# man_actuation_board_2_4.net
KiCad netlist of a schematic drawn in EAGLE
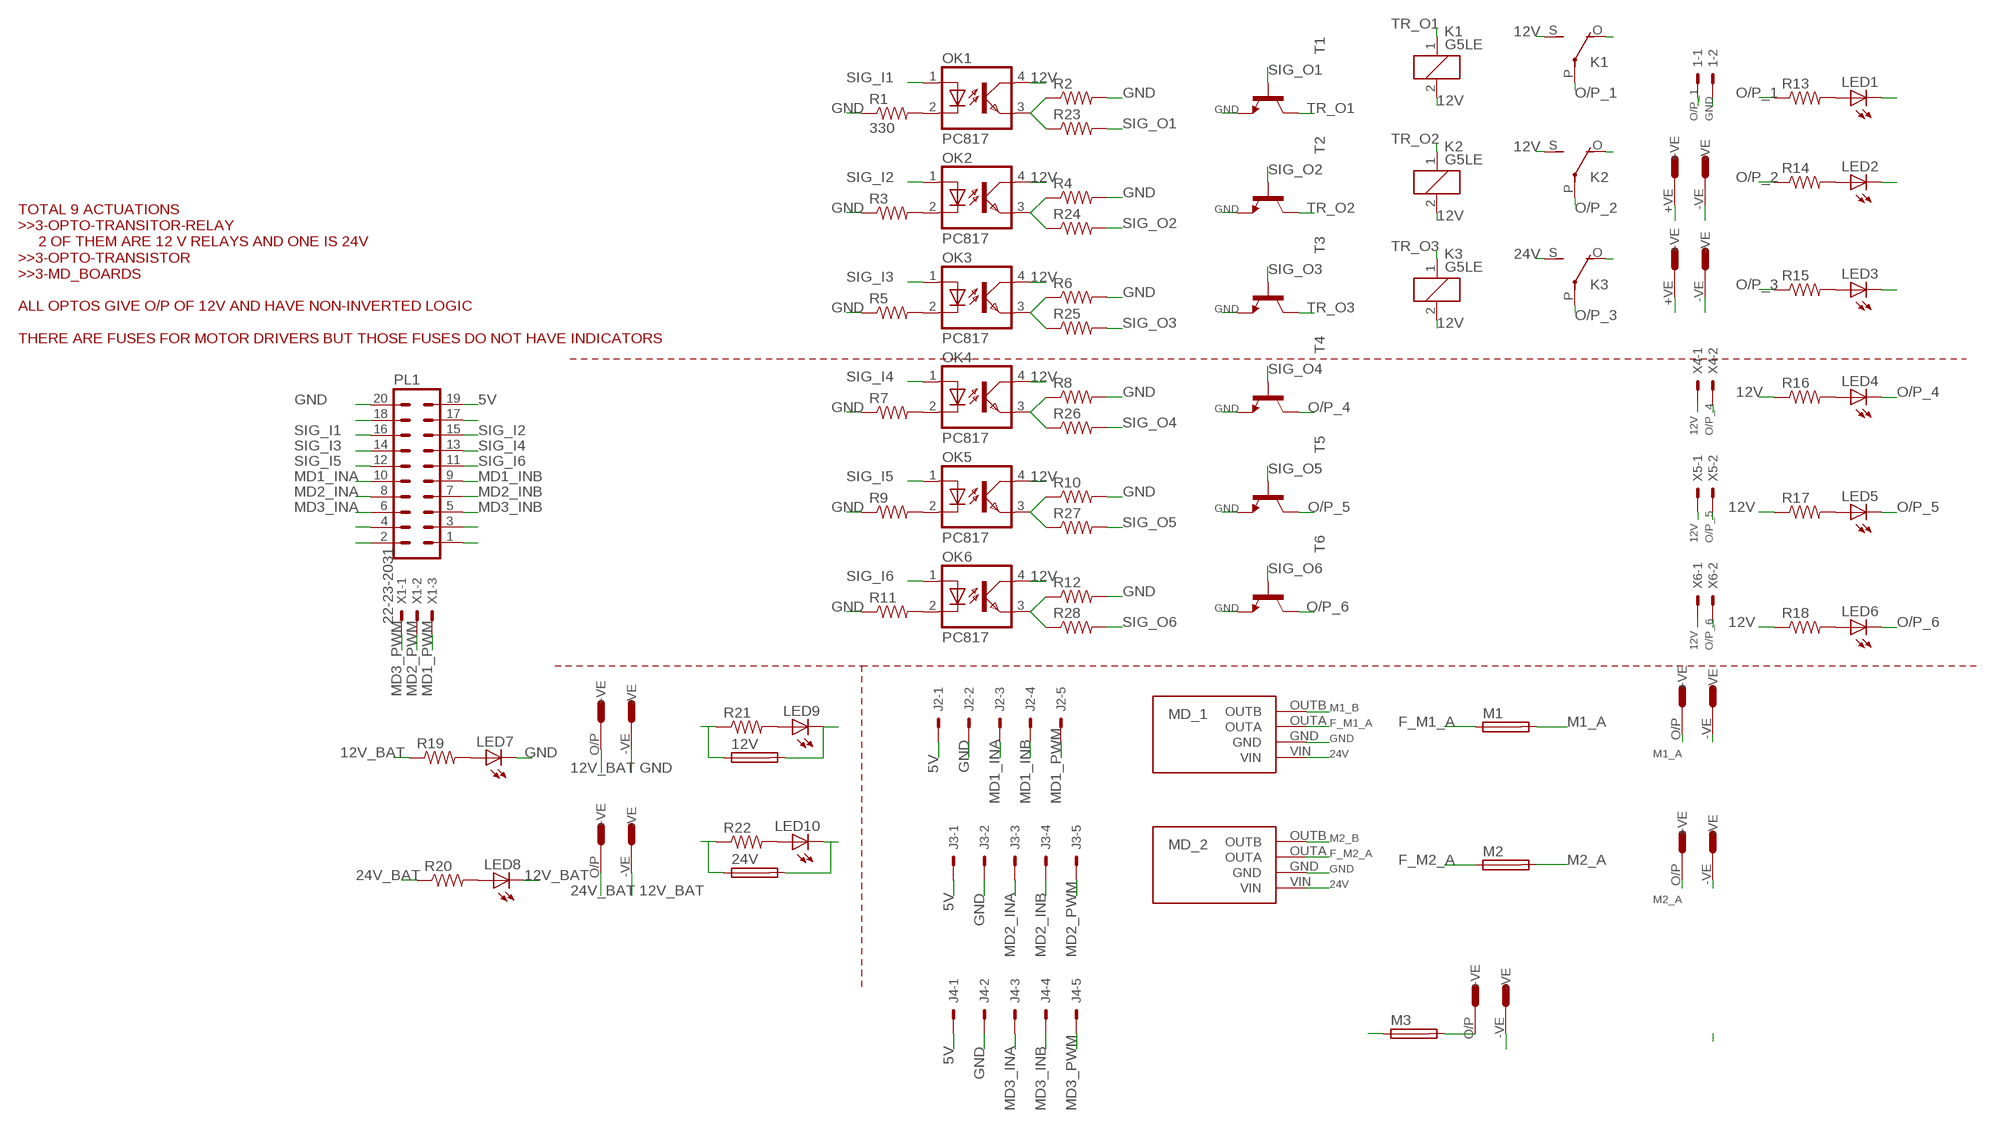
[diagram p0: schematic, sheet 1]

(export (version "E")
  (design (tool "Eeschema 10.0.6"))
  (components
    (comp (ref "0-12_BAT")
      (value "MOLEX_4")
      (footprint "eagle-import:MOLEX_2K14")
      (libsource (lib "eagle-import") (part "MOLEX_4"))
    )
    (comp (ref "1")
      (value "1")
      (footprint "eagle-import:22-23-2021")
      (fields (field (name "MF") "MOLEX") (field (name "MPN") "22-23-2021"))
      (libsource (lib "eagle-import") (part "22-23-2021"))
    )
    (comp (ref "12-24_I/P")
      (value "MOLEX_4")
      (footprint "eagle-import:MOLEX_2K14")
      (libsource (lib "eagle-import") (part "MOLEX_4"))
    )
    (comp (ref "12V")
      (value "SH25")
      (footprint "eagle-import:SH25")
      (fields (field (name "MF") "SCHURTER") (field (name "MPN") "0031.8211"))
      (libsource (lib "eagle-import") (part "SH25"))
    )
    (comp (ref "24V")
      (value "SH25")
      (footprint "eagle-import:SH25")
      (fields (field (name "MF") "SCHURTER") (field (name "MPN") "0031.8211"))
      (libsource (lib "eagle-import") (part "SH25"))
    )
    (comp (ref "J2")
      (value "22-27-2051-05")
      (footprint "eagle-import:6410-05")
      (libsource (lib "eagle-import") (part "22-?-0527-2051"))
    )
    (comp (ref "J3")
      (value "22-27-2051-05")
      (footprint "eagle-import:6410-05")
      (libsource (lib "eagle-import") (part "22-?-0527-2051"))
    )
    (comp (ref "J4")
      (value "22-27-2051-05")
      (footprint "eagle-import:6410-05")
      (libsource (lib "eagle-import") (part "22-?-0527-2051"))
    )
    (comp (ref "K1")
      (value "G5LE")
      (footprint "eagle-import:G5LE")
      (libsource (lib "eagle-import") (part "G5LE"))
    )
    (comp (ref "K2")
      (value "G5LE")
      (footprint "eagle-import:G5LE")
      (libsource (lib "eagle-import") (part "G5LE"))
    )
    (comp (ref "K3")
      (value "G5LE")
      (footprint "eagle-import:G5LE")
      (libsource (lib "eagle-import") (part "G5LE"))
    )
    (comp (ref "LED1")
      (value "LED1206")
      (footprint "eagle-import:LED-1206")
      (libsource (lib "eagle-import") (part "LED1206"))
    )
    (comp (ref "LED2")
      (value "LED1206")
      (footprint "eagle-import:LED-1206")
      (libsource (lib "eagle-import") (part "LED1206"))
    )
    (comp (ref "LED3")
      (value "LED1206")
      (footprint "eagle-import:LED-1206")
      (libsource (lib "eagle-import") (part "LED1206"))
    )
    (comp (ref "LED4")
      (value "LED1206")
      (footprint "eagle-import:LED-1206")
      (libsource (lib "eagle-import") (part "LED1206"))
    )
    (comp (ref "LED5")
      (value "LED1206")
      (footprint "eagle-import:LED-1206")
      (libsource (lib "eagle-import") (part "LED1206"))
    )
    (comp (ref "LED6")
      (value "LED1206")
      (footprint "eagle-import:LED-1206")
      (libsource (lib "eagle-import") (part "LED1206"))
    )
    (comp (ref "LED7")
      (value "LED1206")
      (footprint "eagle-import:LED-1206")
      (libsource (lib "eagle-import") (part "LED1206"))
    )
    (comp (ref "LED8")
      (value "LED1206")
      (footprint "eagle-import:LED-1206")
      (libsource (lib "eagle-import") (part "LED1206"))
    )
    (comp (ref "LED9")
      (value "LED1206")
      (footprint "eagle-import:LED-1206")
      (libsource (lib "eagle-import") (part "LED1206"))
    )
    (comp (ref "LED10")
      (value "LED1206")
      (footprint "eagle-import:LED-1206")
      (libsource (lib "eagle-import") (part "LED1206"))
    )
    (comp (ref "M1")
      (value "SH25")
      (footprint "eagle-import:SH25")
      (fields (field (name "MF") "SCHURTER") (field (name "MPN") "0031.8211"))
      (libsource (lib "eagle-import") (part "SH25"))
    )
    (comp (ref "M2")
      (value "SH25")
      (footprint "eagle-import:SH25")
      (fields (field (name "MF") "SCHURTER") (field (name "MPN") "0031.8211"))
      (libsource (lib "eagle-import") (part "SH25"))
    )
    (comp (ref "M3")
      (value "SH25")
      (footprint "eagle-import:SH25")
      (fields (field (name "MF") "SCHURTER") (field (name "MPN") "0031.8211"))
      (libsource (lib "eagle-import") (part "SH25"))
    )
    (comp (ref "MD_1")
      (value "MOTOR_DRIVER")
      (footprint "eagle-import:MOTOR_DRIVER")
      (libsource (lib "eagle-import") (part "MOTOR_DRIVER"))
    )
    (comp (ref "MD_2")
      (value "MOTOR_DRIVER")
      (footprint "eagle-import:MOTOR_DRIVER")
      (libsource (lib "eagle-import") (part "MOTOR_DRIVER"))
    )
    (comp (ref "OK1")
      (value "PC817")
      (footprint "eagle-import:DIL04")
      (fields (field (name "MPN") "PC817X4J000F"))
      (libsource (lib "eagle-import") (part "PC817"))
    )
    (comp (ref "OK2")
      (value "PC817")
      (footprint "eagle-import:DIL04")
      (fields (field (name "MPN") "PC817X4J000F"))
      (libsource (lib "eagle-import") (part "PC817"))
    )
    (comp (ref "OK3")
      (value "PC817")
      (footprint "eagle-import:DIL04")
      (fields (field (name "MPN") "PC817X4J000F"))
      (libsource (lib "eagle-import") (part "PC817"))
    )
    (comp (ref "OK4")
      (value "PC817")
      (footprint "eagle-import:DIL04")
      (fields (field (name "MPN") "PC817X4J000F"))
      (libsource (lib "eagle-import") (part "PC817"))
    )
    (comp (ref "OK5")
      (value "PC817")
      (footprint "eagle-import:DIL04")
      (fields (field (name "MPN") "PC817X4J000F"))
      (libsource (lib "eagle-import") (part "PC817"))
    )
    (comp (ref "OK6")
      (value "PC817")
      (footprint "eagle-import:DIL04")
      (fields (field (name "MPN") "PC817X4J000F"))
      (libsource (lib "eagle-import") (part "PC817"))
    )
    (comp (ref "PL1")
      (value "ML20ML20")
      (footprint "eagle-import:ML20")
      (libsource (lib "eagle-import") (part "ML20ML20"))
    )
    (comp (ref "R1")
      (value "330")
      (footprint "eagle-import:1206")
      (libsource (lib "eagle-import") (part "RESISTOR1206"))
    )
    (comp (ref "R2")
      (value "RESISTOR1206")
      (footprint "eagle-import:1206")
      (libsource (lib "eagle-import") (part "RESISTOR1206"))
    )
    (comp (ref "R3")
      (value "RESISTOR1206")
      (footprint "eagle-import:1206")
      (libsource (lib "eagle-import") (part "RESISTOR1206"))
    )
    (comp (ref "R4")
      (value "RESISTOR1206")
      (footprint "eagle-import:1206")
      (libsource (lib "eagle-import") (part "RESISTOR1206"))
    )
    (comp (ref "R5")
      (value "RESISTOR1206")
      (footprint "eagle-import:1206")
      (libsource (lib "eagle-import") (part "RESISTOR1206"))
    )
    (comp (ref "R6")
      (value "RESISTOR1206")
      (footprint "eagle-import:1206")
      (libsource (lib "eagle-import") (part "RESISTOR1206"))
    )
    (comp (ref "R7")
      (value "RESISTOR1206")
      (footprint "eagle-import:1206")
      (libsource (lib "eagle-import") (part "RESISTOR1206"))
    )
    (comp (ref "R8")
      (value "RESISTOR1206")
      (footprint "eagle-import:1206")
      (libsource (lib "eagle-import") (part "RESISTOR1206"))
    )
    (comp (ref "R9")
      (value "RESISTOR1206")
      (footprint "eagle-import:1206")
      (libsource (lib "eagle-import") (part "RESISTOR1206"))
    )
    (comp (ref "R10")
      (value "RESISTOR1206")
      (footprint "eagle-import:1206")
      (libsource (lib "eagle-import") (part "RESISTOR1206"))
    )
    (comp (ref "R11")
      (value "RESISTOR1206")
      (footprint "eagle-import:1206")
      (libsource (lib "eagle-import") (part "RESISTOR1206"))
    )
    (comp (ref "R12")
      (value "RESISTOR1206")
      (footprint "eagle-import:1206")
      (libsource (lib "eagle-import") (part "RESISTOR1206"))
    )
    (comp (ref "R13")
      (value "RESISTOR1206")
      (footprint "eagle-import:1206")
      (libsource (lib "eagle-import") (part "RESISTOR1206"))
    )
    (comp (ref "R14")
      (value "RESISTOR1206")
      (footprint "eagle-import:1206")
      (libsource (lib "eagle-import") (part "RESISTOR1206"))
    )
    (comp (ref "R15")
      (value "RESISTOR1206")
      (footprint "eagle-import:1206")
      (libsource (lib "eagle-import") (part "RESISTOR1206"))
    )
    (comp (ref "R16")
      (value "RESISTOR1206")
      (footprint "eagle-import:1206")
      (libsource (lib "eagle-import") (part "RESISTOR1206"))
    )
    (comp (ref "R17")
      (value "RESISTOR1206")
      (footprint "eagle-import:1206")
      (libsource (lib "eagle-import") (part "RESISTOR1206"))
    )
    (comp (ref "R18")
      (value "RESISTOR1206")
      (footprint "eagle-import:1206")
      (libsource (lib "eagle-import") (part "RESISTOR1206"))
    )
    (comp (ref "R19")
      (value "RESISTOR1206")
      (footprint "eagle-import:1206")
      (libsource (lib "eagle-import") (part "RESISTOR1206"))
    )
    (comp (ref "R20")
      (value "RESISTOR1206")
      (footprint "eagle-import:1206")
      (libsource (lib "eagle-import") (part "RESISTOR1206"))
    )
    (comp (ref "R21")
      (value "RESISTOR1206")
      (footprint "eagle-import:1206")
      (libsource (lib "eagle-import") (part "RESISTOR1206"))
    )
    (comp (ref "R22")
      (value "RESISTOR1206")
      (footprint "eagle-import:1206")
      (libsource (lib "eagle-import") (part "RESISTOR1206"))
    )
    (comp (ref "R23")
      (value "RESISTOR1206")
      (footprint "eagle-import:1206")
      (libsource (lib "eagle-import") (part "RESISTOR1206"))
    )
    (comp (ref "R24")
      (value "RESISTOR1206")
      (footprint "eagle-import:1206")
      (libsource (lib "eagle-import") (part "RESISTOR1206"))
    )
    (comp (ref "R25")
      (value "RESISTOR1206")
      (footprint "eagle-import:1206")
      (libsource (lib "eagle-import") (part "RESISTOR1206"))
    )
    (comp (ref "R26")
      (value "RESISTOR1206")
      (footprint "eagle-import:1206")
      (libsource (lib "eagle-import") (part "RESISTOR1206"))
    )
    (comp (ref "R27")
      (value "RESISTOR1206")
      (footprint "eagle-import:1206")
      (libsource (lib "eagle-import") (part "RESISTOR1206"))
    )
    (comp (ref "R28")
      (value "RESISTOR1206")
      (footprint "eagle-import:1206")
      (libsource (lib "eagle-import") (part "RESISTOR1206"))
    )
    (comp (ref "T1")
      (value "-NPN-TO5")
      (footprint "eagle-import:TO5")
      (libsource (lib "eagle-import") (part "-NPN-TO5"))
    )
    (comp (ref "T2")
      (value "-NPN-TO5")
      (footprint "eagle-import:TO5")
      (libsource (lib "eagle-import") (part "-NPN-TO5"))
    )
    (comp (ref "T3")
      (value "-NPN-TO5")
      (footprint "eagle-import:TO5")
      (libsource (lib "eagle-import") (part "-NPN-TO5"))
    )
    (comp (ref "T4")
      (value "-NPN-TO5")
      (footprint "eagle-import:TO5")
      (libsource (lib "eagle-import") (part "-NPN-TO5"))
    )
    (comp (ref "T5")
      (value "-NPN-TO5")
      (footprint "eagle-import:TO5")
      (libsource (lib "eagle-import") (part "-NPN-TO5"))
    )
    (comp (ref "T6")
      (value "-NPN-TO5")
      (footprint "eagle-import:TO5")
      (libsource (lib "eagle-import") (part "-NPN-TO5"))
    )
    (comp (ref "U$1")
      (value "MOLEX_4")
      (footprint "eagle-import:MOLEX_2K14")
      (libsource (lib "eagle-import") (part "MOLEX_4"))
    )
    (comp (ref "U$2")
      (value "MOLEX_4")
      (footprint "eagle-import:MOLEX_2K14")
      (libsource (lib "eagle-import") (part "MOLEX_4"))
    )
    (comp (ref "U$3")
      (value "MOLEX_4")
      (footprint "eagle-import:MOLEX_2K14")
      (libsource (lib "eagle-import") (part "MOLEX_4"))
    )
    (comp (ref "U$4")
      (value "MOLEXM")
      (footprint "eagle-import:MOLEX_2K13")
      (libsource (lib "eagle-import") (part "MOLEXM"))
    )
    (comp (ref "U$5")
      (value "MOLEXM")
      (footprint "eagle-import:MOLEX_2K13")
      (libsource (lib "eagle-import") (part "MOLEXM"))
    )
    (comp (ref "X1")
      (value "22-23-2031")
      (footprint "eagle-import:22-23-2031")
      (fields (field (name "MF") "MOLEX"))
      (libsource (lib "eagle-import") (part "22-23-2031"))
    )
    (comp (ref "X4")
      (value "4")
      (footprint "eagle-import:22-23-2021")
      (fields (field (name "MF") "MOLEX") (field (name "MPN") "22-23-2021"))
      (libsource (lib "eagle-import") (part "22-23-2021"))
    )
    (comp (ref "X5")
      (value "5")
      (footprint "eagle-import:22-23-2021")
      (fields (field (name "MF") "MOLEX") (field (name "MPN") "22-23-2021"))
      (libsource (lib "eagle-import") (part "22-23-2021"))
    )
    (comp (ref "X6")
      (value "6")
      (footprint "eagle-import:22-23-2021")
      (fields (field (name "MF") "MOLEX") (field (name "MPN") "22-23-2021"))
      (libsource (lib "eagle-import") (part "22-23-2021"))
    )
  )
  (nets
    (net (code "1") (name "/5V") (class "Default")
      (node (ref "J2") (pin "1") (pinfunction "S_1") (pintype "passive"))
      (node (ref "J3") (pin "1") (pinfunction "S_1") (pintype "passive"))
      (node (ref "J4") (pin "1") (pinfunction "S_1") (pintype "passive"))
      (node (ref "PL1") (pin "19") (pinfunction "19_19") (pintype "passive"))
    )
    (net (code "2") (name "/12V") (class "Default")
      (node (ref "12V") (pin "2") (pinfunction "2_2") (pintype "passive"))
      (node (ref "K1") (pin "2") (pinfunction "2_2") (pintype "passive"))
      (node (ref "K1") (pin "S") (pinfunction "S_S") (pintype "passive"))
      (node (ref "K2") (pin "2") (pinfunction "2_2") (pintype "passive"))
      (node (ref "K2") (pin "S") (pinfunction "S_S") (pintype "passive"))
      (node (ref "K3") (pin "2") (pinfunction "2_2") (pintype "passive"))
      (node (ref "LED9") (pin "C") (pinfunction "C_C") (pintype "passive"))
      (node (ref "OK1") (pin "4") (pinfunction "COL_4") (pintype "passive"))
      (node (ref "OK2") (pin "4") (pinfunction "COL_4") (pintype "passive"))
      (node (ref "OK3") (pin "4") (pinfunction "COL_4") (pintype "passive"))
      (node (ref "OK4") (pin "4") (pinfunction "COL_4") (pintype "passive"))
      (node (ref "OK5") (pin "4") (pinfunction "COL_4") (pintype "passive"))
      (node (ref "OK6") (pin "4") (pinfunction "COL_4") (pintype "passive"))
      (node (ref "R16") (pin "1") (pinfunction "1_1") (pintype "passive"))
      (node (ref "R17") (pin "1") (pinfunction "1_1") (pintype "passive"))
      (node (ref "R18") (pin "1") (pinfunction "1_1") (pintype "passive"))
      (node (ref "X4") (pin "1") (pinfunction "S_1") (pintype "passive"))
      (node (ref "X5") (pin "1") (pinfunction "S_1") (pintype "passive"))
      (node (ref "X6") (pin "1") (pinfunction "S_1") (pintype "passive"))
    )
    (net (code "3") (name "/12V_BAT") (class "Default")
      (node (ref "0-12_BAT") (pin "O/P") (pinfunction "+VE_O/P") (pintype "bidirectional"))
      (node (ref "12-24_I/P") (pin "-VE") (pinfunction "-VE_-VE") (pintype "bidirectional"))
      (node (ref "12V") (pin "1") (pinfunction "1_1") (pintype "passive"))
      (node (ref "LED8") (pin "C") (pinfunction "C_C") (pintype "passive"))
      (node (ref "R19") (pin "1") (pinfunction "1_1") (pintype "passive"))
      (node (ref "R21") (pin "1") (pinfunction "1_1") (pintype "passive"))
    )
    (net (code "4") (name "/24V") (class "Default")
      (node (ref "24V") (pin "2") (pinfunction "2_2") (pintype "passive"))
      (node (ref "K3") (pin "S") (pinfunction "S_S") (pintype "passive"))
      (node (ref "LED10") (pin "C") (pinfunction "C_C") (pintype "passive"))
      (node (ref "M3") (pin "1") (pinfunction "1_1") (pintype "passive"))
      (node (ref "MD_1") (pin "VIN") (pinfunction "VIN_VIN") (pintype "bidirectional"))
      (node (ref "MD_2") (pin "VIN") (pinfunction "VIN_VIN") (pintype "bidirectional"))
    )
    (net (code "5") (name "/24V_BAT") (class "Default")
      (node (ref "12-24_I/P") (pin "O/P") (pinfunction "+VE_O/P") (pintype "bidirectional"))
      (node (ref "24V") (pin "1") (pinfunction "1_1") (pintype "passive"))
      (node (ref "R20") (pin "1") (pinfunction "1_1") (pintype "passive"))
      (node (ref "R22") (pin "1") (pinfunction "1_1") (pintype "passive"))
    )
    (net (code "6") (name "/F_M1_A") (class "Default")
      (node (ref "M1") (pin "1") (pinfunction "1_1") (pintype "passive"))
      (node (ref "MD_1") (pin "OUTA") (pinfunction "OUTA_OUTA") (pintype "bidirectional"))
    )
    (net (code "7") (name "/F_M2_A") (class "Default")
      (node (ref "M2") (pin "1") (pinfunction "1_1") (pintype "passive"))
      (node (ref "MD_2") (pin "OUTA") (pinfunction "OUTA_OUTA") (pintype "bidirectional"))
    )
    (net (code "8") (name "/GND") (class "Default")
      (node (ref "0-12_BAT") (pin "-VE") (pinfunction "-VE_-VE") (pintype "bidirectional"))
      (node (ref "1") (pin "2") (pinfunction "S_2") (pintype "passive"))
      (node (ref "J2") (pin "2") (pinfunction "S_2") (pintype "passive"))
      (node (ref "J3") (pin "2") (pinfunction "S_2") (pintype "passive"))
      (node (ref "J4") (pin "2") (pinfunction "S_2") (pintype "passive"))
      (node (ref "LED1") (pin "C") (pinfunction "C_C") (pintype "passive"))
      (node (ref "LED2") (pin "C") (pinfunction "C_C") (pintype "passive"))
      (node (ref "LED3") (pin "C") (pinfunction "C_C") (pintype "passive"))
      (node (ref "LED7") (pin "C") (pinfunction "C_C") (pintype "passive"))
      (node (ref "MD_1") (pin "GND") (pinfunction "GND_GND") (pintype "bidirectional"))
      (node (ref "MD_2") (pin "GND") (pinfunction "GND_GND") (pintype "bidirectional"))
      (node (ref "PL1") (pin "20") (pinfunction "20_20") (pintype "passive"))
      (node (ref "R1") (pin "1") (pinfunction "1_1") (pintype "passive"))
      (node (ref "R10") (pin "2") (pinfunction "2_2") (pintype "passive"))
      (node (ref "R11") (pin "1") (pinfunction "1_1") (pintype "passive"))
      (node (ref "R12") (pin "2") (pinfunction "2_2") (pintype "passive"))
      (node (ref "R2") (pin "2") (pinfunction "2_2") (pintype "passive"))
      (node (ref "R3") (pin "1") (pinfunction "1_1") (pintype "passive"))
      (node (ref "R4") (pin "2") (pinfunction "2_2") (pintype "passive"))
      (node (ref "R5") (pin "1") (pinfunction "1_1") (pintype "passive"))
      (node (ref "R6") (pin "2") (pinfunction "2_2") (pintype "passive"))
      (node (ref "R7") (pin "1") (pinfunction "1_1") (pintype "passive"))
      (node (ref "R8") (pin "2") (pinfunction "2_2") (pintype "passive"))
      (node (ref "R9") (pin "1") (pinfunction "1_1") (pintype "passive"))
      (node (ref "T1") (pin "1") (pinfunction "E_1") (pintype "passive"))
      (node (ref "T2") (pin "1") (pinfunction "E_1") (pintype "passive"))
      (node (ref "T3") (pin "1") (pinfunction "E_1") (pintype "passive"))
      (node (ref "T4") (pin "1") (pinfunction "E_1") (pintype "passive"))
      (node (ref "T5") (pin "1") (pinfunction "E_1") (pintype "passive"))
      (node (ref "T6") (pin "1") (pinfunction "E_1") (pintype "passive"))
      (node (ref "U$3") (pin "-VE") (pinfunction "-VE_-VE") (pintype "bidirectional"))
      (node (ref "U$4") (pin "-VE") (pinfunction "-VE_-VE") (pintype "bidirectional"))
      (node (ref "U$5") (pin "-VE") (pinfunction "-VE_-VE") (pintype "bidirectional"))
    )
    (net (code "9") (name "/M1_A") (class "Default")
      (node (ref "M1") (pin "2") (pinfunction "2_2") (pintype "passive"))
      (node (ref "U$1") (pin "O/P") (pinfunction "+VE_O/P") (pintype "bidirectional"))
    )
    (net (code "10") (name "/M1_B") (class "Default")
      (node (ref "MD_1") (pin "OUTB") (pinfunction "OUTB_OUTB") (pintype "bidirectional"))
      (node (ref "U$1") (pin "-VE") (pinfunction "-VE_-VE") (pintype "bidirectional"))
    )
    (net (code "11") (name "/M2_A") (class "Default")
      (node (ref "M2") (pin "2") (pinfunction "2_2") (pintype "passive"))
      (node (ref "U$2") (pin "O/P") (pinfunction "+VE_O/P") (pintype "bidirectional"))
    )
    (net (code "12") (name "/M2_B") (class "Default")
      (node (ref "MD_2") (pin "OUTB") (pinfunction "OUTB_OUTB") (pintype "bidirectional"))
      (node (ref "U$2") (pin "-VE") (pinfunction "-VE_-VE") (pintype "bidirectional"))
    )
    (net (code "13") (name "/MD1_INA") (class "Default")
      (node (ref "J2") (pin "3") (pinfunction "S_3") (pintype "passive"))
      (node (ref "PL1") (pin "10") (pinfunction "10_10") (pintype "passive"))
    )
    (net (code "14") (name "/MD1_INB") (class "Default")
      (node (ref "J2") (pin "4") (pinfunction "S_4") (pintype "passive"))
      (node (ref "PL1") (pin "9") (pinfunction "9_9") (pintype "passive"))
    )
    (net (code "15") (name "/MD1_PWM") (class "Default")
      (node (ref "J2") (pin "5") (pinfunction "S_5") (pintype "passive"))
      (node (ref "X1") (pin "3") (pinfunction "S_3") (pintype "passive"))
    )
    (net (code "16") (name "/MD2_INA") (class "Default")
      (node (ref "J3") (pin "3") (pinfunction "S_3") (pintype "passive"))
      (node (ref "PL1") (pin "8") (pinfunction "8_8") (pintype "passive"))
    )
    (net (code "17") (name "/MD2_INB") (class "Default")
      (node (ref "J3") (pin "4") (pinfunction "S_4") (pintype "passive"))
      (node (ref "PL1") (pin "7") (pinfunction "7_7") (pintype "passive"))
    )
    (net (code "18") (name "/MD2_PWM") (class "Default")
      (node (ref "J3") (pin "5") (pinfunction "S_5") (pintype "passive"))
      (node (ref "X1") (pin "2") (pinfunction "S_2") (pintype "passive"))
    )
    (net (code "19") (name "/MD3_INA") (class "Default")
      (node (ref "J4") (pin "3") (pinfunction "S_3") (pintype "passive"))
      (node (ref "PL1") (pin "6") (pinfunction "6_6") (pintype "passive"))
    )
    (net (code "20") (name "/MD3_INB") (class "Default")
      (node (ref "J4") (pin "4") (pinfunction "S_4") (pintype "passive"))
      (node (ref "PL1") (pin "5") (pinfunction "5_5") (pintype "passive"))
    )
    (net (code "21") (name "/MD3_PWM") (class "Default")
      (node (ref "J4") (pin "5") (pinfunction "S_5") (pintype "passive"))
      (node (ref "X1") (pin "1") (pinfunction "S_1") (pintype "passive"))
    )
    (net (code "22") (name "/O{slash}P_1") (class "Default")
      (node (ref "1") (pin "1") (pinfunction "S_1") (pintype "passive"))
      (node (ref "K1") (pin "P") (pinfunction "P_P") (pintype "passive"))
      (node (ref "R13") (pin "1") (pinfunction "1_1") (pintype "passive"))
    )
    (net (code "23") (name "/O{slash}P_2") (class "Default")
      (node (ref "K2") (pin "P") (pinfunction "P_P") (pintype "passive"))
      (node (ref "R14") (pin "1") (pinfunction "1_1") (pintype "passive"))
      (node (ref "U$5") (pin "+VE") (pinfunction "+VE_+VE") (pintype "bidirectional"))
    )
    (net (code "24") (name "/O{slash}P_3") (class "Default")
      (node (ref "K3") (pin "P") (pinfunction "P_P") (pintype "passive"))
      (node (ref "R15") (pin "1") (pinfunction "1_1") (pintype "passive"))
      (node (ref "U$4") (pin "+VE") (pinfunction "+VE_+VE") (pintype "bidirectional"))
    )
    (net (code "25") (name "/O{slash}P_4") (class "Default")
      (node (ref "LED4") (pin "C") (pinfunction "C_C") (pintype "passive"))
      (node (ref "T4") (pin "3") (pinfunction "C_3") (pintype "passive"))
      (node (ref "X4") (pin "2") (pinfunction "S_2") (pintype "passive"))
    )
    (net (code "26") (name "/O{slash}P_5") (class "Default")
      (node (ref "LED5") (pin "C") (pinfunction "C_C") (pintype "passive"))
      (node (ref "T5") (pin "3") (pinfunction "C_3") (pintype "passive"))
      (node (ref "X5") (pin "2") (pinfunction "S_2") (pintype "passive"))
    )
    (net (code "27") (name "/O{slash}P_6") (class "Default")
      (node (ref "LED6") (pin "C") (pinfunction "C_C") (pintype "passive"))
      (node (ref "T6") (pin "3") (pinfunction "C_3") (pintype "passive"))
      (node (ref "X6") (pin "2") (pinfunction "S_2") (pintype "passive"))
    )
    (net (code "28") (name "/SIG_I1") (class "Default")
      (node (ref "OK1") (pin "1") (pinfunction "A_1") (pintype "passive"))
      (node (ref "PL1") (pin "16") (pinfunction "16_16") (pintype "passive"))
    )
    (net (code "29") (name "/SIG_I2") (class "Default")
      (node (ref "OK2") (pin "1") (pinfunction "A_1") (pintype "passive"))
      (node (ref "PL1") (pin "15") (pinfunction "15_15") (pintype "passive"))
    )
    (net (code "30") (name "/SIG_I3") (class "Default")
      (node (ref "OK3") (pin "1") (pinfunction "A_1") (pintype "passive"))
      (node (ref "PL1") (pin "14") (pinfunction "14_14") (pintype "passive"))
    )
    (net (code "31") (name "/SIG_I4") (class "Default")
      (node (ref "OK4") (pin "1") (pinfunction "A_1") (pintype "passive"))
      (node (ref "PL1") (pin "13") (pinfunction "13_13") (pintype "passive"))
    )
    (net (code "32") (name "/SIG_I5") (class "Default")
      (node (ref "OK5") (pin "1") (pinfunction "A_1") (pintype "passive"))
      (node (ref "PL1") (pin "12") (pinfunction "12_12") (pintype "passive"))
    )
    (net (code "33") (name "/SIG_I6") (class "Default")
      (node (ref "OK6") (pin "1") (pinfunction "A_1") (pintype "passive"))
      (node (ref "PL1") (pin "11") (pinfunction "11_11") (pintype "passive"))
    )
    (net (code "34") (name "/SIG_O1") (class "Default")
      (node (ref "R23") (pin "2") (pinfunction "2_2") (pintype "passive"))
      (node (ref "T1") (pin "2") (pinfunction "B_2") (pintype "passive"))
    )
    (net (code "35") (name "/SIG_O2") (class "Default")
      (node (ref "R24") (pin "2") (pinfunction "2_2") (pintype "passive"))
      (node (ref "T2") (pin "2") (pinfunction "B_2") (pintype "passive"))
    )
    (net (code "36") (name "/SIG_O3") (class "Default")
      (node (ref "R25") (pin "2") (pinfunction "2_2") (pintype "passive"))
      (node (ref "T3") (pin "2") (pinfunction "B_2") (pintype "passive"))
    )
    (net (code "37") (name "/SIG_O4") (class "Default")
      (node (ref "R26") (pin "2") (pinfunction "2_2") (pintype "passive"))
      (node (ref "T4") (pin "2") (pinfunction "B_2") (pintype "passive"))
    )
    (net (code "38") (name "/SIG_O5") (class "Default")
      (node (ref "R27") (pin "2") (pinfunction "2_2") (pintype "passive"))
      (node (ref "T5") (pin "2") (pinfunction "B_2") (pintype "passive"))
    )
    (net (code "39") (name "/SIG_O6") (class "Default")
      (node (ref "R28") (pin "2") (pinfunction "2_2") (pintype "passive"))
      (node (ref "T6") (pin "2") (pinfunction "B_2") (pintype "passive"))
    )
    (net (code "40") (name "/TR_O1") (class "Default")
      (node (ref "K1") (pin "1") (pinfunction "1_1") (pintype "passive"))
      (node (ref "T1") (pin "3") (pinfunction "C_3") (pintype "passive"))
    )
    (net (code "41") (name "/TR_O2") (class "Default")
      (node (ref "K2") (pin "1") (pinfunction "1_1") (pintype "passive"))
      (node (ref "T2") (pin "3") (pinfunction "C_3") (pintype "passive"))
    )
    (net (code "42") (name "/TR_O3") (class "Default")
      (node (ref "K3") (pin "1") (pinfunction "1_1") (pintype "passive"))
      (node (ref "T3") (pin "3") (pinfunction "C_3") (pintype "passive"))
    )
    (net (code "43") (name "Net-(LED1-PadA)") (class "Default")
      (node (ref "LED1") (pin "A") (pinfunction "A_A") (pintype "passive"))
      (node (ref "R13") (pin "2") (pinfunction "2_2") (pintype "passive"))
    )
    (net (code "44") (name "Net-(LED2-PadA)") (class "Default")
      (node (ref "LED2") (pin "A") (pinfunction "A_A") (pintype "passive"))
      (node (ref "R14") (pin "2") (pinfunction "2_2") (pintype "passive"))
    )
    (net (code "45") (name "Net-(LED3-PadA)") (class "Default")
      (node (ref "LED3") (pin "A") (pinfunction "A_A") (pintype "passive"))
      (node (ref "R15") (pin "2") (pinfunction "2_2") (pintype "passive"))
    )
    (net (code "46") (name "Net-(LED4-PadA)") (class "Default")
      (node (ref "LED4") (pin "A") (pinfunction "A_A") (pintype "passive"))
      (node (ref "R16") (pin "2") (pinfunction "2_2") (pintype "passive"))
    )
    (net (code "47") (name "Net-(LED5-PadA)") (class "Default")
      (node (ref "LED5") (pin "A") (pinfunction "A_A") (pintype "passive"))
      (node (ref "R17") (pin "2") (pinfunction "2_2") (pintype "passive"))
    )
    (net (code "48") (name "Net-(LED6-PadA)") (class "Default")
      (node (ref "LED6") (pin "A") (pinfunction "A_A") (pintype "passive"))
      (node (ref "R18") (pin "2") (pinfunction "2_2") (pintype "passive"))
    )
    (net (code "49") (name "Net-(LED7-PadA)") (class "Default")
      (node (ref "LED7") (pin "A") (pinfunction "A_A") (pintype "passive"))
      (node (ref "R19") (pin "2") (pinfunction "2_2") (pintype "passive"))
    )
    (net (code "50") (name "Net-(LED8-PadA)") (class "Default")
      (node (ref "LED8") (pin "A") (pinfunction "A_A") (pintype "passive"))
      (node (ref "R20") (pin "2") (pinfunction "2_2") (pintype "passive"))
    )
    (net (code "51") (name "Net-(LED9-PadA)") (class "Default")
      (node (ref "LED9") (pin "A") (pinfunction "A_A") (pintype "passive"))
      (node (ref "R21") (pin "2") (pinfunction "2_2") (pintype "passive"))
    )
    (net (code "52") (name "Net-(LED10-PadA)") (class "Default")
      (node (ref "LED10") (pin "A") (pinfunction "A_A") (pintype "passive"))
      (node (ref "R22") (pin "2") (pinfunction "2_2") (pintype "passive"))
    )
    (net (code "53") (name "Net-(OK1-C)") (class "Default")
      (node (ref "OK1") (pin "2") (pinfunction "C_2") (pintype "passive"))
      (node (ref "R1") (pin "2") (pinfunction "2_2") (pintype "passive"))
    )
    (net (code "54") (name "Net-(OK1-EMIT)") (class "Default")
      (node (ref "OK1") (pin "3") (pinfunction "EMIT_3") (pintype "passive"))
      (node (ref "R2") (pin "1") (pinfunction "1_1") (pintype "passive"))
      (node (ref "R23") (pin "1") (pinfunction "1_1") (pintype "passive"))
    )
    (net (code "55") (name "Net-(OK2-C)") (class "Default")
      (node (ref "OK2") (pin "2") (pinfunction "C_2") (pintype "passive"))
      (node (ref "R3") (pin "2") (pinfunction "2_2") (pintype "passive"))
    )
    (net (code "56") (name "Net-(OK2-EMIT)") (class "Default")
      (node (ref "OK2") (pin "3") (pinfunction "EMIT_3") (pintype "passive"))
      (node (ref "R24") (pin "1") (pinfunction "1_1") (pintype "passive"))
      (node (ref "R4") (pin "1") (pinfunction "1_1") (pintype "passive"))
    )
    (net (code "57") (name "Net-(OK3-C)") (class "Default")
      (node (ref "OK3") (pin "2") (pinfunction "C_2") (pintype "passive"))
      (node (ref "R5") (pin "2") (pinfunction "2_2") (pintype "passive"))
    )
    (net (code "58") (name "Net-(OK3-EMIT)") (class "Default")
      (node (ref "OK3") (pin "3") (pinfunction "EMIT_3") (pintype "passive"))
      (node (ref "R25") (pin "1") (pinfunction "1_1") (pintype "passive"))
      (node (ref "R6") (pin "1") (pinfunction "1_1") (pintype "passive"))
    )
    (net (code "59") (name "Net-(OK4-C)") (class "Default")
      (node (ref "OK4") (pin "2") (pinfunction "C_2") (pintype "passive"))
      (node (ref "R7") (pin "2") (pinfunction "2_2") (pintype "passive"))
    )
    (net (code "60") (name "Net-(OK4-EMIT)") (class "Default")
      (node (ref "OK4") (pin "3") (pinfunction "EMIT_3") (pintype "passive"))
      (node (ref "R26") (pin "1") (pinfunction "1_1") (pintype "passive"))
      (node (ref "R8") (pin "1") (pinfunction "1_1") (pintype "passive"))
    )
    (net (code "61") (name "Net-(OK5-C)") (class "Default")
      (node (ref "OK5") (pin "2") (pinfunction "C_2") (pintype "passive"))
      (node (ref "R9") (pin "2") (pinfunction "2_2") (pintype "passive"))
    )
    (net (code "62") (name "Net-(OK5-EMIT)") (class "Default")
      (node (ref "OK5") (pin "3") (pinfunction "EMIT_3") (pintype "passive"))
      (node (ref "R10") (pin "1") (pinfunction "1_1") (pintype "passive"))
      (node (ref "R27") (pin "1") (pinfunction "1_1") (pintype "passive"))
    )
    (net (code "63") (name "Net-(OK6-C)") (class "Default")
      (node (ref "OK6") (pin "2") (pinfunction "C_2") (pintype "passive"))
      (node (ref "R11") (pin "2") (pinfunction "2_2") (pintype "passive"))
    )
    (net (code "64") (name "Net-(OK6-EMIT)") (class "Default")
      (node (ref "OK6") (pin "3") (pinfunction "EMIT_3") (pintype "passive"))
      (node (ref "R12") (pin "1") (pinfunction "1_1") (pintype "passive"))
      (node (ref "R28") (pin "1") (pinfunction "1_1") (pintype "passive"))
    )
    (net (code "65") (name "Net-(U$3-+VE)") (class "Default")
      (node (ref "M3") (pin "2") (pinfunction "2_2") (pintype "passive"))
      (node (ref "U$3") (pin "O/P") (pinfunction "+VE_O/P") (pintype "bidirectional"))
    )
    (net (code "66") (name "unconnected-(K1-PadO)") (class "Default")
      (node (ref "K1") (pin "O") (pinfunction "O_O") (pintype "passive"))
    )
    (net (code "67") (name "unconnected-(K2-PadO)") (class "Default")
      (node (ref "K2") (pin "O") (pinfunction "O_O") (pintype "passive"))
    )
    (net (code "68") (name "unconnected-(K3-PadO)") (class "Default")
      (node (ref "K3") (pin "O") (pinfunction "O_O") (pintype "passive"))
    )
    (net (code "69") (name "unconnected-(PL1-Pad1)") (class "Default")
      (node (ref "PL1") (pin "1") (pinfunction "1_1") (pintype "passive"))
    )
    (net (code "70") (name "unconnected-(PL1-Pad2)") (class "Default")
      (node (ref "PL1") (pin "2") (pinfunction "2_2") (pintype "passive"))
    )
    (net (code "71") (name "unconnected-(PL1-Pad3)") (class "Default")
      (node (ref "PL1") (pin "3") (pinfunction "3_3") (pintype "passive"))
    )
    (net (code "72") (name "unconnected-(PL1-Pad4)") (class "Default")
      (node (ref "PL1") (pin "4") (pinfunction "4_4") (pintype "passive"))
    )
    (net (code "73") (name "unconnected-(PL1-Pad17)") (class "Default")
      (node (ref "PL1") (pin "17") (pinfunction "17_17") (pintype "passive"))
    )
    (net (code "74") (name "unconnected-(PL1-Pad18)") (class "Default")
      (node (ref "PL1") (pin "18") (pinfunction "18_18") (pintype "passive"))
    )
  )
)
